# counter-defender-featherwing-mk-1_2.net
KiCad netlist of a schematic drawn in EAGLE
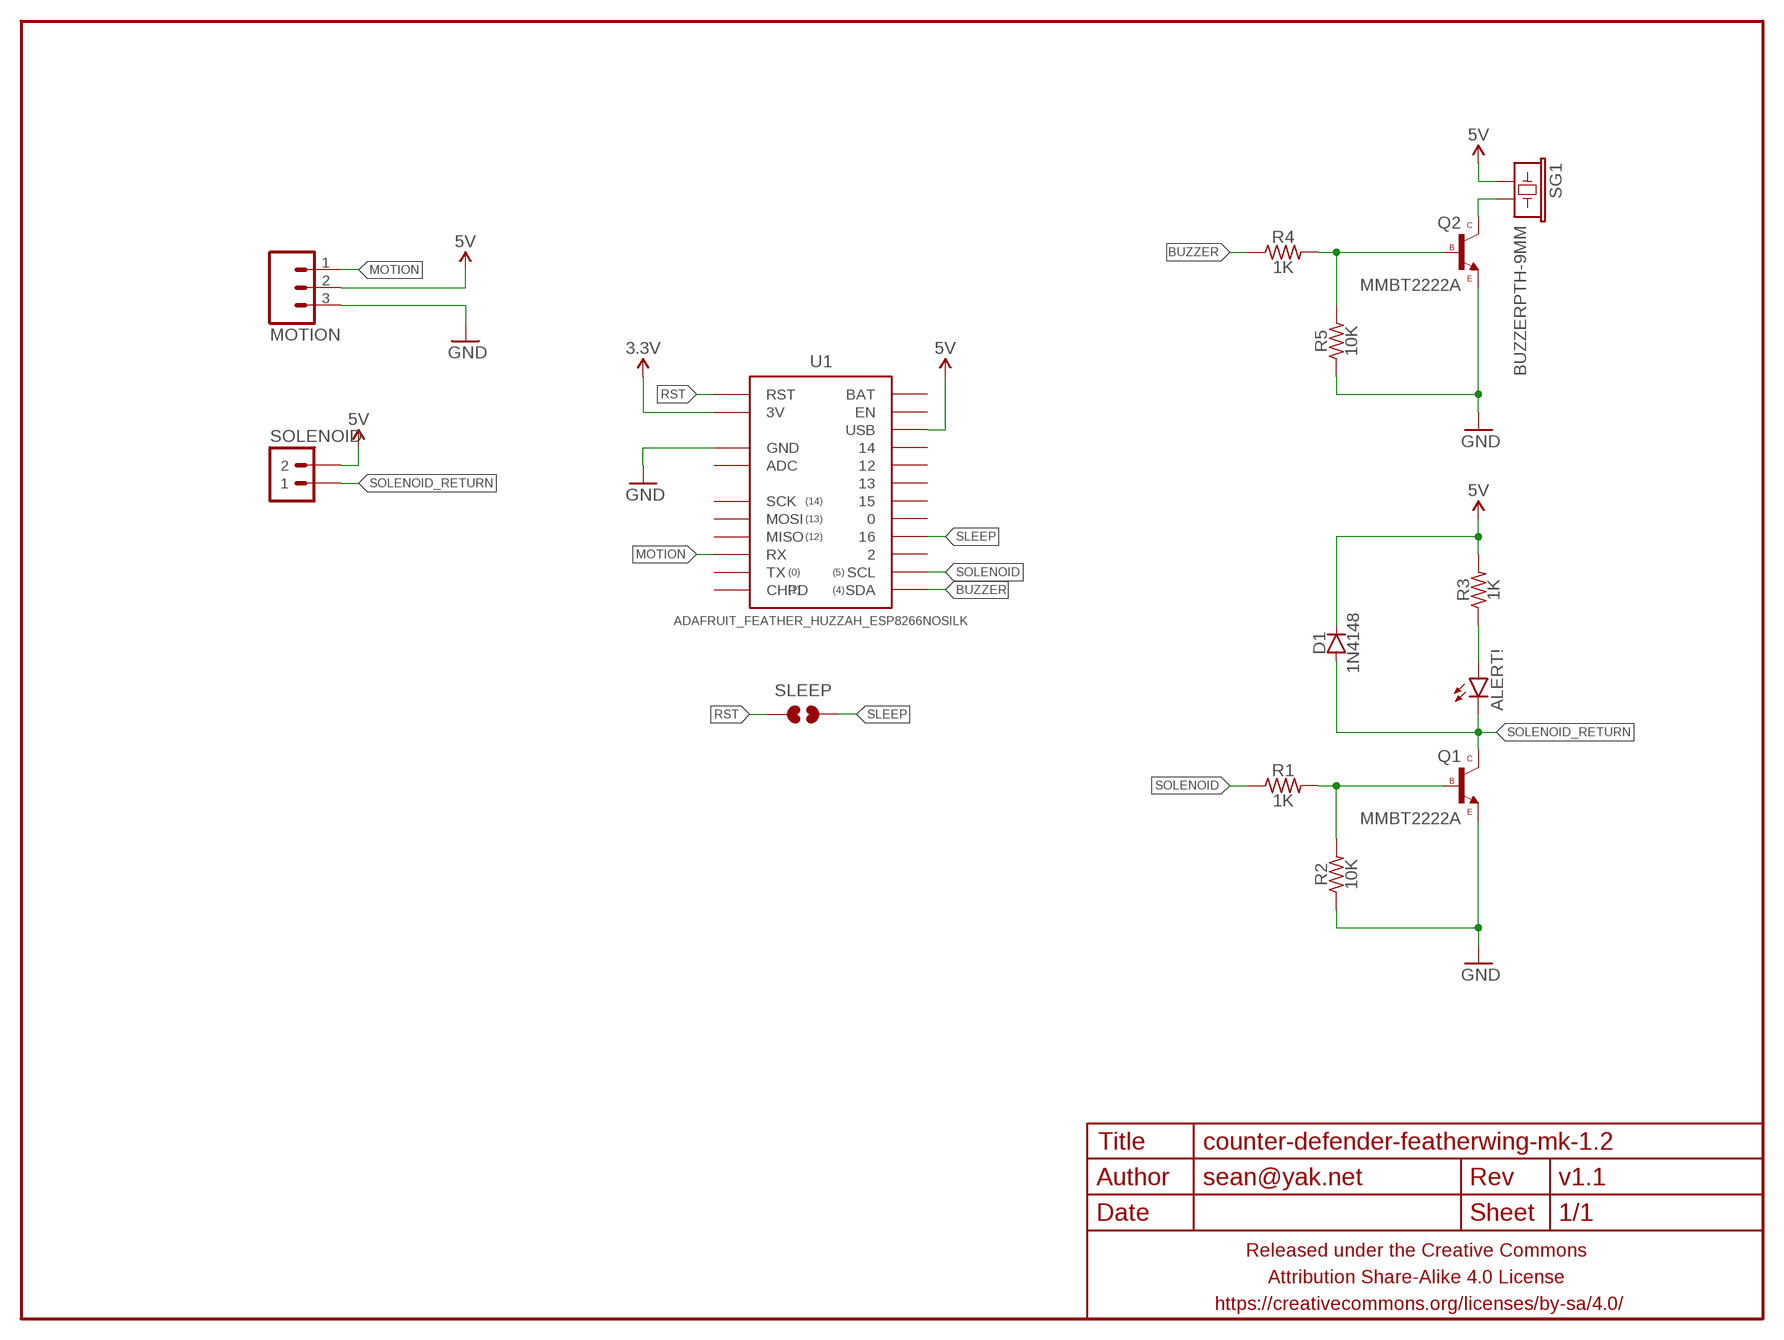
[diagram p0: schematic, sheet 1]

(export (version "E")
  (design (tool "Eeschema 10.0.6"))
  (components
    (comp (ref "ALERT!")
      (value "LED0603-TIGHT")
      (footprint "eagle-import:LED-0603-TIGHT")
      (libsource (lib "eagle-import") (part "LED0603-TIGHT"))
    )
    (comp (ref "D1")
      (value "1N4148")
      (footprint "eagle-import:SOD123")
      (libsource (lib "eagle-import") (part "DIODESOD123"))
    )
    (comp (ref "FRAME1")
      (value "FRAME-LETTERNO_PACKAGE")
      (footprint "eagle-import:DUMMY")
      (fields (field (name "DESIGNER") "sean@yak.net") (field (name "VERSION") "v1.1"))
      (libsource (lib "eagle-import") (part "FRAME-LETTERNO_PACKAGE"))
    )
    (comp (ref "MOTION")
      (value "M03PTH-CENTERED")
      (footprint "eagle-import:1X03-CENTERED")
      (libsource (lib "eagle-import") (part "M03PTH-CENTERED"))
    )
    (comp (ref "Q1")
      (value "MMBT2222A")
      (footprint "eagle-import:SOT23")
      (libsource (lib "eagle-import") (part "TRANSISTOR_NPNMMBT2222A"))
    )
    (comp (ref "Q2")
      (value "MMBT2222A")
      (footprint "eagle-import:SOT23")
      (libsource (lib "eagle-import") (part "TRANSISTOR_NPNMMBT2222A"))
    )
    (comp (ref "R1")
      (value "1K")
      (footprint "eagle-import:R0603-TIGHTER")
      (libsource (lib "eagle-import") (part "RESISTORR0603-TIGHTER"))
    )
    (comp (ref "R2")
      (value "10K")
      (footprint "eagle-import:R0603-TIGHTER")
      (libsource (lib "eagle-import") (part "RESISTORR0603-TIGHTER"))
    )
    (comp (ref "R3")
      (value "1K")
      (footprint "eagle-import:R0603-TIGHTER")
      (libsource (lib "eagle-import") (part "RESISTORR0603-TIGHTER"))
    )
    (comp (ref "R4")
      (value "1K")
      (footprint "eagle-import:R0603-TIGHTER")
      (libsource (lib "eagle-import") (part "RESISTORR0603-TIGHTER"))
    )
    (comp (ref "R5")
      (value "10K")
      (footprint "eagle-import:R0603-TIGHTER")
      (libsource (lib "eagle-import") (part "RESISTORR0603-TIGHTER"))
    )
    (comp (ref "SG1")
      (value "BUZZERPTH-9MM")
      (footprint "eagle-import:BUZZER-PTH-9MM")
      (libsource (lib "eagle-import") (part "BUZZERPTH-9MM"))
    )
    (comp (ref "SLEEP")
      (value "JUMPER-PAD-2-NOYES_SILK")
      (footprint "eagle-import:PAD-JUMPER-2-NO_YES_SILK")
      (libsource (lib "eagle-import") (part "JUMPER-PAD-2-NOYES_SILK"))
    )
    (comp (ref "SOLENOID")
      (value "M02PTH-CENTERED")
      (footprint "eagle-import:1X02-CENTER")
      (libsource (lib "eagle-import") (part "M02PTH-CENTERED"))
    )
    (comp (ref "U1")
      (value "ADAFRUIT_FEATHER_HUZZAH_ESP8266NOSILK")
      (footprint "eagle-import:ADAFRUIT_FEATHER_HUZZAH_NOSILK")
      (libsource (lib "eagle-import") (part "ADAFRUIT_FEATHER_HUZZAH_ESP8266NOSILK"))
    )
  )
  (nets
    (net (code "1") (name "3.3V") (class "Default")
      (node (ref "U1") (pin "3V") (pinfunction "3V_3V") (pintype "bidirectional"))
    )
    (net (code "2") (name "5V") (class "Default")
      (node (ref "D1") (pin "C") (pinfunction "C_C") (pintype "passive"))
      (node (ref "MOTION") (pin "2") (pinfunction "2_2") (pintype "passive"))
      (node (ref "R3") (pin "2") (pinfunction "2_2") (pintype "passive"))
      (node (ref "SG1") (pin "+") (pinfunction "1_+") (pintype "passive"))
      (node (ref "SOLENOID") (pin "2") (pinfunction "2_2") (pintype "passive"))
      (node (ref "U1") (pin "USB") (pinfunction "USB_USB") (pintype "bidirectional"))
    )
    (net (code "3") (name "BUZZER") (class "Default")
      (node (ref "R4") (pin "1") (pinfunction "1_1") (pintype "passive"))
      (node (ref "U1") (pin "SDA") (pinfunction "SDA_SDA") (pintype "bidirectional"))
    )
    (net (code "4") (name "GND") (class "Default")
      (node (ref "MOTION") (pin "3") (pinfunction "3_3") (pintype "passive"))
      (node (ref "Q1") (pin "2") (pinfunction "E_2") (pintype "passive"))
      (node (ref "Q2") (pin "2") (pinfunction "E_2") (pintype "passive"))
      (node (ref "R2") (pin "1") (pinfunction "1_1") (pintype "passive"))
      (node (ref "R5") (pin "1") (pinfunction "1_1") (pintype "passive"))
      (node (ref "U1") (pin "GND@0") (pinfunction "GND_GND@0") (pintype "bidirectional"))
    )
    (net (code "5") (name "MOTION") (class "Default")
      (node (ref "MOTION") (pin "1") (pinfunction "1_1") (pintype "passive"))
      (node (ref "U1") (pin "RX") (pinfunction "RX_RX") (pintype "bidirectional"))
    )
    (net (code "6") (name "Net-(ALERT!-PadA)") (class "Default")
      (node (ref "ALERT!") (pin "A") (pinfunction "A_A") (pintype "passive"))
      (node (ref "R3") (pin "1") (pinfunction "1_1") (pintype "passive"))
    )
    (net (code "7") (name "Net-(Q1-B)") (class "Default")
      (node (ref "Q1") (pin "1") (pinfunction "B_1") (pintype "passive"))
      (node (ref "R1") (pin "2") (pinfunction "2_2") (pintype "passive"))
      (node (ref "R2") (pin "2") (pinfunction "2_2") (pintype "passive"))
    )
    (net (code "8") (name "Net-(Q2-B)") (class "Default")
      (node (ref "Q2") (pin "1") (pinfunction "B_1") (pintype "passive"))
      (node (ref "R4") (pin "2") (pinfunction "2_2") (pintype "passive"))
      (node (ref "R5") (pin "2") (pinfunction "2_2") (pintype "passive"))
    )
    (net (code "9") (name "Net-(Q2-C)") (class "Default")
      (node (ref "Q2") (pin "3") (pinfunction "C_3") (pintype "passive"))
      (node (ref "SG1") (pin "-") (pinfunction "2_-") (pintype "passive"))
    )
    (net (code "10") (name "RST") (class "Default")
      (node (ref "SLEEP") (pin "1") (pinfunction "1_1") (pintype "passive"))
      (node (ref "U1") (pin "RST") (pinfunction "RST_RST") (pintype "bidirectional"))
    )
    (net (code "11") (name "SLEEP") (class "Default")
      (node (ref "SLEEP") (pin "2") (pinfunction "2_2") (pintype "passive"))
      (node (ref "U1") (pin "16") (pinfunction "16_16") (pintype "bidirectional"))
    )
    (net (code "12") (name "SOLENOID") (class "Default")
      (node (ref "R1") (pin "1") (pinfunction "1_1") (pintype "passive"))
      (node (ref "U1") (pin "SCL") (pinfunction "SCL_SCL") (pintype "bidirectional"))
    )
    (net (code "13") (name "SOLENOID_RETURN") (class "Default")
      (node (ref "ALERT!") (pin "C") (pinfunction "C_C") (pintype "passive"))
      (node (ref "D1") (pin "A") (pinfunction "A_A") (pintype "passive"))
      (node (ref "Q1") (pin "3") (pinfunction "C_3") (pintype "passive"))
      (node (ref "SOLENOID") (pin "1") (pinfunction "1_1") (pintype "passive"))
    )
    (net (code "14") (name "unconnected-(U1-Pad0)") (class "Default")
      (node (ref "U1") (pin "0") (pinfunction "0_0") (pintype "bidirectional"))
    )
    (net (code "15") (name "unconnected-(U1-Pad2)") (class "Default")
      (node (ref "U1") (pin "2") (pinfunction "2_2") (pintype "bidirectional"))
    )
    (net (code "16") (name "unconnected-(U1-Pad12)") (class "Default")
      (node (ref "U1") (pin "12") (pinfunction "12_12") (pintype "bidirectional"))
    )
    (net (code "17") (name "unconnected-(U1-Pad13)") (class "Default")
      (node (ref "U1") (pin "13") (pinfunction "13_13") (pintype "bidirectional"))
    )
    (net (code "18") (name "unconnected-(U1-Pad14)") (class "Default")
      (node (ref "U1") (pin "14") (pinfunction "14_14") (pintype "bidirectional"))
    )
    (net (code "19") (name "unconnected-(U1-Pad15)") (class "Default")
      (node (ref "U1") (pin "15") (pinfunction "15_15") (pintype "bidirectional"))
    )
    (net (code "20") (name "unconnected-(U1-PadADC)") (class "Default")
      (node (ref "U1") (pin "ADC") (pinfunction "ADC_ADC") (pintype "bidirectional"))
    )
    (net (code "21") (name "unconnected-(U1-PadBAT)") (class "Default")
      (node (ref "U1") (pin "BAT") (pinfunction "BAT_BAT") (pintype "bidirectional"))
    )
    (net (code "22") (name "unconnected-(U1-PadCHPD)") (class "Default")
      (node (ref "U1") (pin "CHPD") (pinfunction "CHPD_CHPD") (pintype "bidirectional"))
    )
    (net (code "23") (name "unconnected-(U1-PadEN)") (class "Default")
      (node (ref "U1") (pin "EN") (pinfunction "EN_EN") (pintype "bidirectional"))
    )
    (net (code "24") (name "unconnected-(U1-PadMISO)") (class "Default")
      (node (ref "U1") (pin "MISO") (pinfunction "MISO_MISO") (pintype "bidirectional"))
    )
    (net (code "25") (name "unconnected-(U1-PadMOSI)") (class "Default")
      (node (ref "U1") (pin "MOSI") (pinfunction "MOSI_MOSI") (pintype "bidirectional"))
    )
    (net (code "26") (name "unconnected-(U1-PadSCK)") (class "Default")
      (node (ref "U1") (pin "SCK") (pinfunction "SCK_SCK") (pintype "bidirectional"))
    )
    (net (code "27") (name "unconnected-(U1-PadTX)") (class "Default")
      (node (ref "U1") (pin "TX") (pinfunction "TX_TX") (pintype "bidirectional"))
    )
  )
)
